# BufferOut.net
KiCad netlist of a schematic drawn in Altium Designer
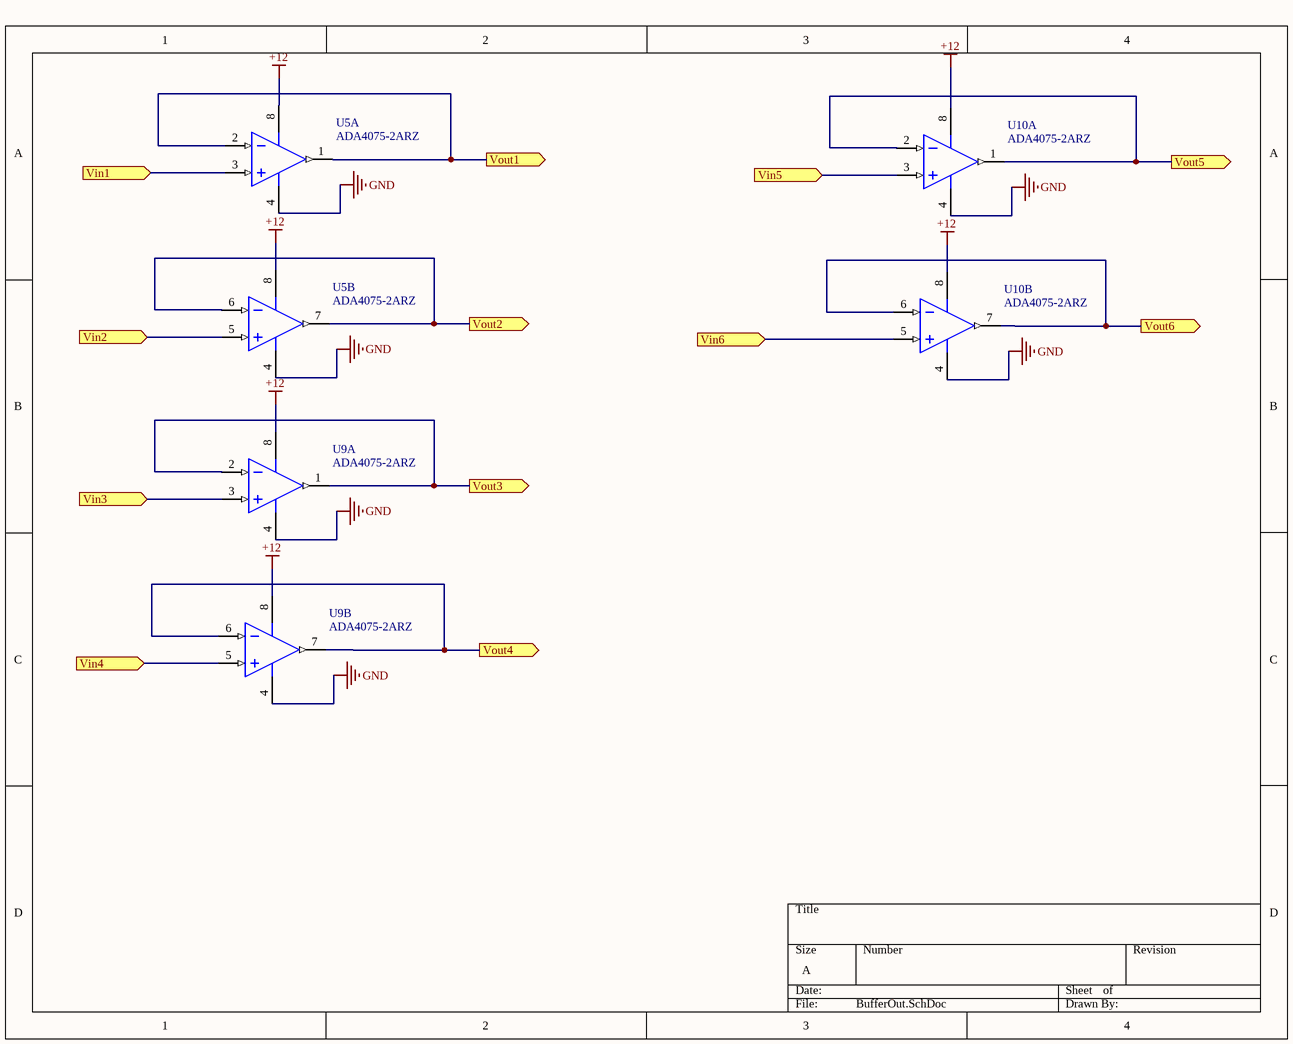
[diagram p0: BufferOut.SchDoc]

(export (version "E")
  (design (tool "Eeschema 10.0.6"))
  (components
    (comp (ref "U5")
      (value "ADA4075-2ARZ")
      (footprint "ADI-R-8_N")
      (fields (field (name "MANUFACTURER") "Analog Devices") (field (name "GENERIC PART NUMBER") "ADA4075-2"))
      (libsource (lib "Altium Content Vault") (part "ADI-OP29X-R-8"))
    )
    (comp (ref "U9")
      (value "ADA4075-2ARZ")
      (footprint "ADI-R-8_N")
      (fields (field (name "MANUFACTURER") "Analog Devices") (field (name "GENERIC PART NUMBER") "ADA4075-2"))
      (libsource (lib "Altium Content Vault") (part "ADI-OP29X-R-8"))
    )
    (comp (ref "U10")
      (value "ADA4075-2ARZ")
      (footprint "ADI-R-8_N")
      (fields (field (name "MANUFACTURER") "Analog Devices") (field (name "GENERIC PART NUMBER") "ADA4075-2"))
      (libsource (lib "Altium Content Vault") (part "ADI-OP29X-R-8"))
    )
  )
  (nets
    (net (code "1") (name "+12") (class "Default")
      (node (ref "U10") (pin "8") (pinfunction "+V_8") (pintype "power_in"))
      (node (ref "U5") (pin "8") (pinfunction "+V_8") (pintype "power_in"))
      (node (ref "U9") (pin "8") (pinfunction "+V_8") (pintype "power_in"))
    )
    (net (code "2") (name "/Vin1") (class "Default")
      (node (ref "U5") (pin "3") (pinfunction "+IN_A_3") (pintype "input"))
    )
    (net (code "3") (name "/Vin2") (class "Default")
      (node (ref "U5") (pin "5") (pinfunction "+IN_B_5") (pintype "input"))
    )
    (net (code "4") (name "/Vin3") (class "Default")
      (node (ref "U9") (pin "3") (pinfunction "+IN_A_3") (pintype "input"))
    )
    (net (code "5") (name "/Vin4") (class "Default")
      (node (ref "U9") (pin "5") (pinfunction "+IN_B_5") (pintype "input"))
    )
    (net (code "6") (name "/Vin5") (class "Default")
      (node (ref "U10") (pin "3") (pinfunction "+IN_A_3") (pintype "input"))
    )
    (net (code "7") (name "/Vin6") (class "Default")
      (node (ref "U10") (pin "5") (pinfunction "+IN_B_5") (pintype "input"))
    )
    (net (code "8") (name "/Vout1") (class "Default")
      (node (ref "U5") (pin "1") (pinfunction "OUT_A_1") (pintype "output"))
      (node (ref "U5") (pin "2") (pinfunction "-IN_A_2") (pintype "input"))
    )
    (net (code "9") (name "/Vout2") (class "Default")
      (node (ref "U5") (pin "6") (pinfunction "-IN_B_6") (pintype "input"))
      (node (ref "U5") (pin "7") (pinfunction "OUT_B_7") (pintype "output"))
    )
    (net (code "10") (name "/Vout3") (class "Default")
      (node (ref "U9") (pin "1") (pinfunction "OUT_A_1") (pintype "output"))
      (node (ref "U9") (pin "2") (pinfunction "-IN_A_2") (pintype "input"))
    )
    (net (code "11") (name "/Vout4") (class "Default")
      (node (ref "U9") (pin "6") (pinfunction "-IN_B_6") (pintype "input"))
      (node (ref "U9") (pin "7") (pinfunction "OUT_B_7") (pintype "output"))
    )
    (net (code "12") (name "/Vout5") (class "Default")
      (node (ref "U10") (pin "1") (pinfunction "OUT_A_1") (pintype "output"))
      (node (ref "U10") (pin "2") (pinfunction "-IN_A_2") (pintype "input"))
    )
    (net (code "13") (name "/Vout6") (class "Default")
      (node (ref "U10") (pin "6") (pinfunction "-IN_B_6") (pintype "input"))
      (node (ref "U10") (pin "7") (pinfunction "OUT_B_7") (pintype "output"))
    )
    (net (code "14") (name "GND") (class "Default")
      (node (ref "U10") (pin "4") (pinfunction "-V_4") (pintype "power_in"))
      (node (ref "U5") (pin "4") (pinfunction "-V_4") (pintype "power_in"))
      (node (ref "U9") (pin "4") (pinfunction "-V_4") (pintype "power_in"))
    )
  )
)
